# Control.net
KiCad netlist of a schematic drawn in EAGLE
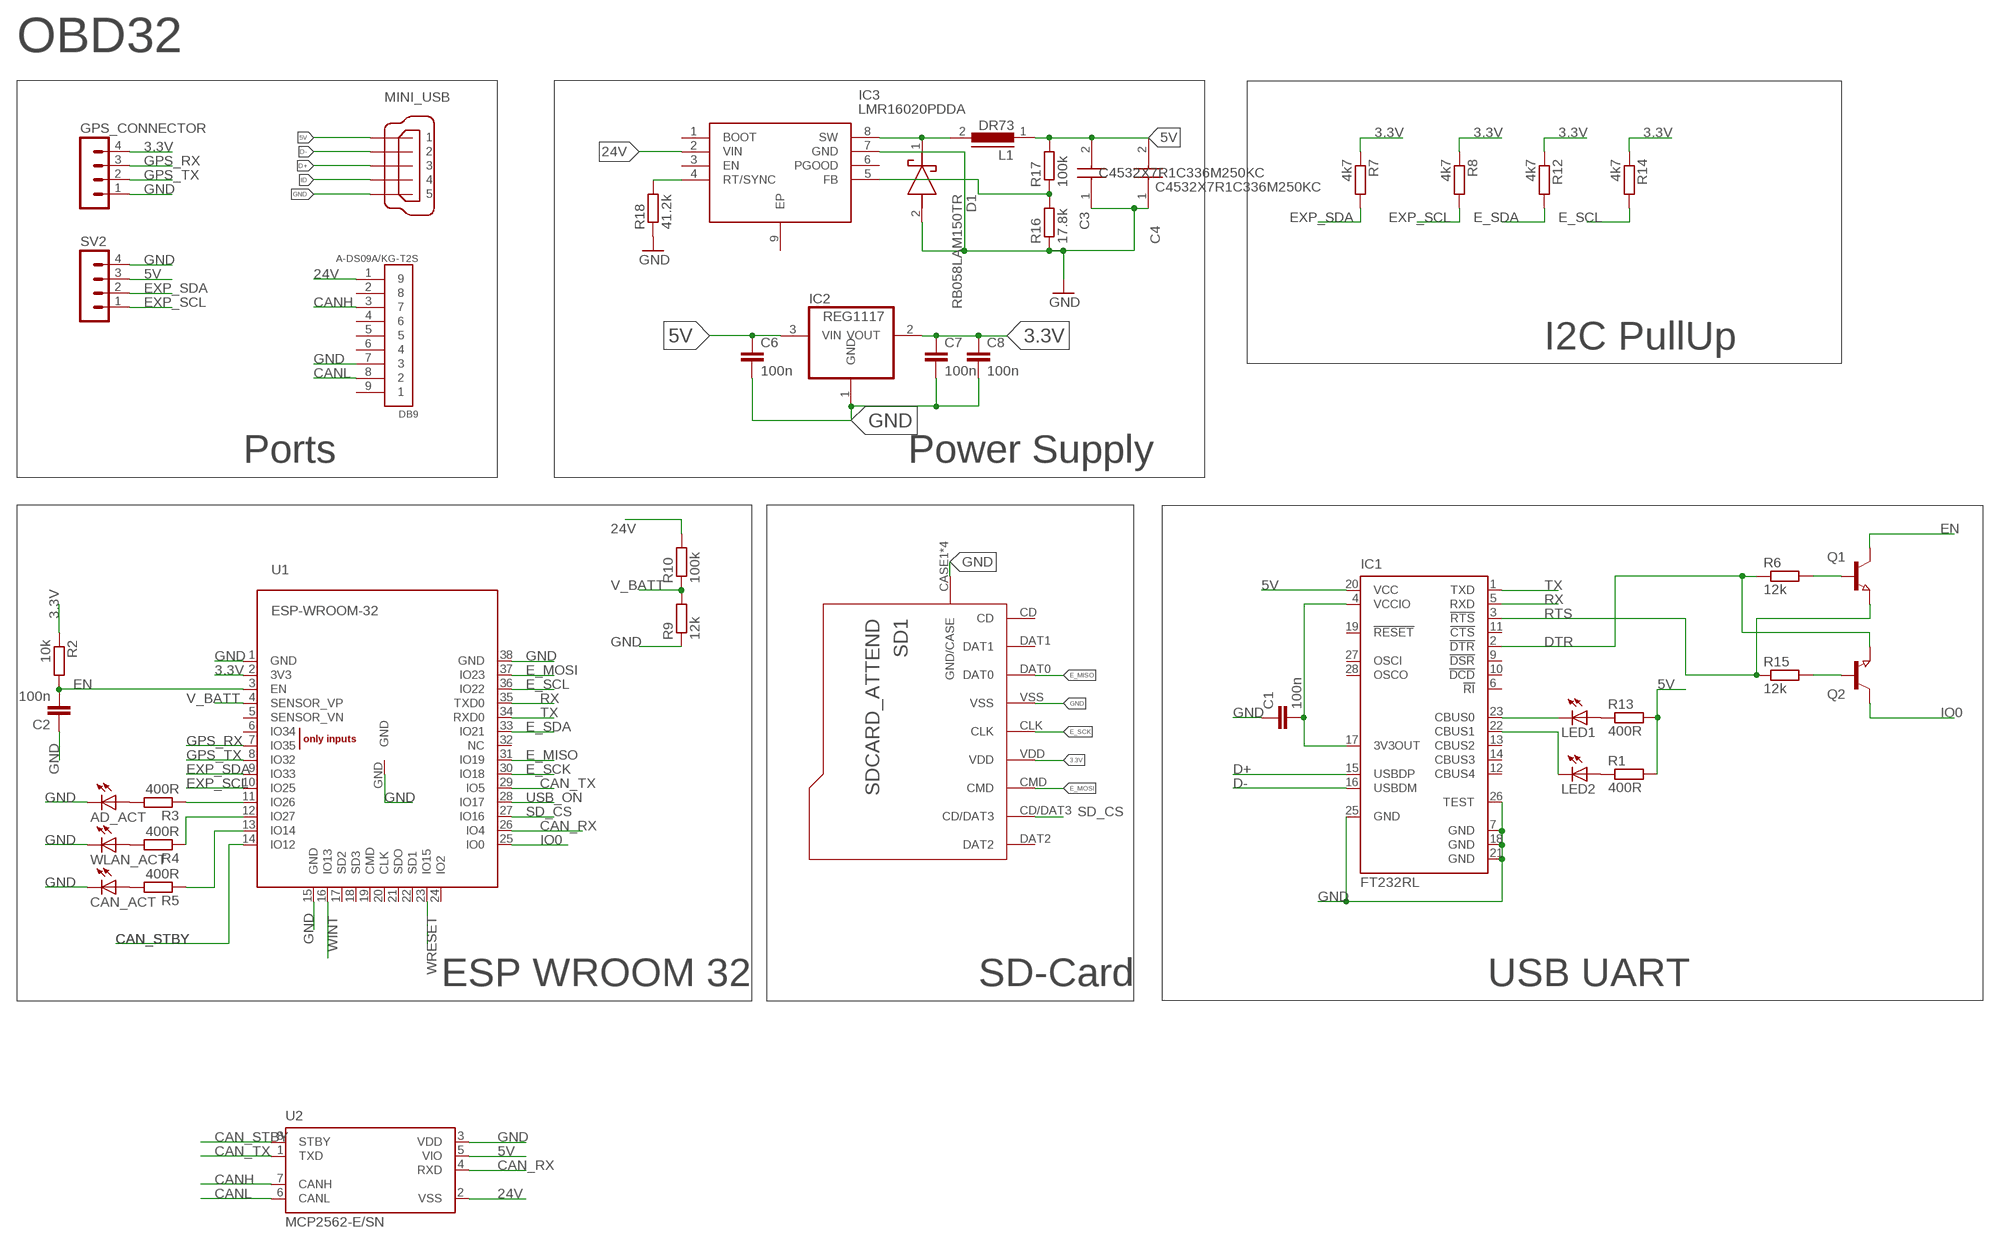
[diagram p0: schematic, sheet 1]

(export (version "E")
  (design (tool "Eeschema 10.0.6"))
  (components
    (comp (ref "AD_ACT")
      (value "LEDCHIP-LED0805")
      (footprint "eagle-import:CHIP-LED0805")
      (libsource (lib "eagle-import") (part "LEDCHIP-LED0805"))
    )
    (comp (ref "C1")
      (value "100n")
      (footprint "eagle-import:C0805")
      (libsource (lib "eagle-import") (part "C-EUC0805"))
    )
    (comp (ref "C2")
      (value "100n")
      (footprint "eagle-import:C0805")
      (libsource (lib "eagle-import") (part "C-EUC0805"))
    )
    (comp (ref "C3")
      (value "C4532X7R1C336M250KC")
      (footprint "eagle-import:CAPC4532X360N")
      (fields (field (name "MOUSER_PART_NUMBER") "810-C4532X7R1C336M"))
      (libsource (lib "eagle-import") (part "C4532X7R1C336M250KC"))
    )
    (comp (ref "C4")
      (value "C4532X7R1C336M250KC")
      (footprint "eagle-import:CAPC4532X360N")
      (fields (field (name "MOUSER_PART_NUMBER") "810-C4532X7R1C336M"))
      (libsource (lib "eagle-import") (part "C4532X7R1C336M250KC"))
    )
    (comp (ref "C6")
      (value "100n")
      (footprint "eagle-import:C0805")
      (libsource (lib "eagle-import") (part "C-EUC0805"))
    )
    (comp (ref "C7")
      (value "100n")
      (footprint "eagle-import:C0805")
      (libsource (lib "eagle-import") (part "C-EUC0805"))
    )
    (comp (ref "C8")
      (value "100n")
      (footprint "eagle-import:C0805")
      (libsource (lib "eagle-import") (part "C-EUC0805"))
    )
    (comp (ref "CAN_ACT")
      (value "LEDCHIP-LED0805")
      (footprint "eagle-import:CHIP-LED0805")
      (libsource (lib "eagle-import") (part "LEDCHIP-LED0805"))
    )
    (comp (ref "D1")
      (value "RB058LAM150TR")
      (footprint "eagle-import:SODFL4725X105N")
      (fields (field (name "MOUSER_PART_NUMBER") "755-RB058LAM150TR"))
      (libsource (lib "eagle-import") (part "RB058LAM150TR"))
    )
    (comp (ref "DB9")
      (value "A-DS09A/KG-T2S")
      (footprint "eagle-import:A-DS09A_KG-T2S")
      (fields
        (field (name "DIGI_KEY_PART_NUMBER") "AE10968-ND")
        (field (name "MANUFACTURER") "Assmann WSW Components")
        (field (name "MPN") "A-DS 09 A/KG-T2S")
        (field (name "CREATEDBY") "PCBLayout.com")
      )
      (libsource (lib "eagle-import") (part "A-DS09A/KG-T2S"))
    )
    (comp (ref "GPS_CONNECTOR")
      (value "MA04-1")
      (footprint "eagle-import:MA04-1")
      (libsource (lib "eagle-import") (part "MA04-1"))
    )
    (comp (ref "IC1")
      (value "FT232RL")
      (footprint "eagle-import:SSOP28")
      (libsource (lib "eagle-import") (part "FT232RL"))
    )
    (comp (ref "IC2")
      (value "REG1117")
      (footprint "eagle-import:SOT223")
      (libsource (lib "eagle-import") (part "REG1117"))
    )
    (comp (ref "IC3")
      (value "LMR16020PDDA")
      (footprint "eagle-import:SOIC127P600X170-9N")
      (fields (field (name "MOUSER_PART_NUMBER") "595-LMR16020PDDA"))
      (libsource (lib "eagle-import") (part "LMR16020PDDA"))
    )
    (comp (ref "L1")
      (value "DR73")
      (footprint "eagle-import:DR73")
      (libsource (lib "eagle-import") (part "DR73"))
    )
    (comp (ref "LED1")
      (value "LEDCHIPLED_0805")
      (footprint "eagle-import:CHIPLED_0805")
      (libsource (lib "eagle-import") (part "LEDCHIPLED_0805"))
    )
    (comp (ref "LED2")
      (value "LEDCHIPLED_0805")
      (footprint "eagle-import:CHIPLED_0805")
      (libsource (lib "eagle-import") (part "LEDCHIPLED_0805"))
    )
    (comp (ref "MINI_USB")
      (value "MINI-USB-32005-301")
      (footprint "eagle-import:32005-301")
      (libsource (lib "eagle-import") (part "MINI-USB-32005-301"))
    )
    (comp (ref "Q1")
      (value "NPN-TRANSISTOR_SOT23")
      (footprint "eagle-import:SOT23")
      (libsource (lib "eagle-import") (part "NPN-TRANSISTOR_SOT23"))
    )
    (comp (ref "Q2")
      (value "NPN-TRANSISTOR_SOT23")
      (footprint "eagle-import:SOT23")
      (libsource (lib "eagle-import") (part "NPN-TRANSISTOR_SOT23"))
    )
    (comp (ref "R1")
      (value "400R")
      (footprint "eagle-import:R0805")
      (libsource (lib "eagle-import") (part "R-EU_R0805"))
    )
    (comp (ref "R2")
      (value "10k")
      (footprint "eagle-import:R0805")
      (libsource (lib "eagle-import") (part "R-EU_R0805"))
    )
    (comp (ref "R3")
      (value "400R")
      (footprint "eagle-import:R0805")
      (libsource (lib "eagle-import") (part "R-EU_R0805"))
    )
    (comp (ref "R4")
      (value "400R")
      (footprint "eagle-import:R0805")
      (libsource (lib "eagle-import") (part "R-EU_R0805"))
    )
    (comp (ref "R5")
      (value "400R")
      (footprint "eagle-import:R0805")
      (libsource (lib "eagle-import") (part "R-EU_R0805"))
    )
    (comp (ref "R6")
      (value "12k")
      (footprint "eagle-import:R0805")
      (libsource (lib "eagle-import") (part "R-EU_R0805"))
    )
    (comp (ref "R7")
      (value "4k7")
      (footprint "eagle-import:R0805")
      (libsource (lib "eagle-import") (part "R-EU_R0805"))
    )
    (comp (ref "R8")
      (value "4k7")
      (footprint "eagle-import:R0805")
      (libsource (lib "eagle-import") (part "R-EU_R0805"))
    )
    (comp (ref "R9")
      (value "12k")
      (footprint "eagle-import:R0805")
      (libsource (lib "eagle-import") (part "R-EU_R0805"))
    )
    (comp (ref "R10")
      (value "100k")
      (footprint "eagle-import:R0805")
      (libsource (lib "eagle-import") (part "R-EU_R0805"))
    )
    (comp (ref "R12")
      (value "4k7")
      (footprint "eagle-import:R0805")
      (libsource (lib "eagle-import") (part "R-EU_R0805"))
    )
    (comp (ref "R13")
      (value "400R")
      (footprint "eagle-import:R0805")
      (libsource (lib "eagle-import") (part "R-EU_R0805"))
    )
    (comp (ref "R14")
      (value "4k7")
      (footprint "eagle-import:R0805")
      (libsource (lib "eagle-import") (part "R-EU_R0805"))
    )
    (comp (ref "R15")
      (value "12k")
      (footprint "eagle-import:R0805")
      (libsource (lib "eagle-import") (part "R-EU_R0805"))
    )
    (comp (ref "R16")
      (value "17.8k")
      (footprint "eagle-import:R0805")
      (libsource (lib "eagle-import") (part "R-EU_R0805"))
    )
    (comp (ref "R17")
      (value "100k")
      (footprint "eagle-import:R0805")
      (libsource (lib "eagle-import") (part "R-EU_R0805"))
    )
    (comp (ref "R18")
      (value "41.2k")
      (footprint "eagle-import:R0805")
      (libsource (lib "eagle-import") (part "R-EU_R0805"))
    )
    (comp (ref "SD1")
      (value "SDCARD_ATTEND")
      (footprint "eagle-import:SD_ATTEND")
      (libsource (lib "eagle-import") (part "SDCARD_ATTEND"))
    )
    (comp (ref "SV2")
      (value "MA04-1")
      (footprint "eagle-import:MA04-1")
      (libsource (lib "eagle-import") (part "MA04-1"))
    )
    (comp (ref "U1")
      (value "ESP-WROOM-32")
      (footprint "eagle-import:ESP-WROOM-32")
      (libsource (lib "eagle-import") (part "ESP-WROOM-32"))
    )
    (comp (ref "U2")
      (value "MCP2562-E/SN")
      (footprint "eagle-import:SOIC127P600X175-8N")
      (fields (field (name "MF") "Microchip"))
      (libsource (lib "eagle-import") (part "MCP2562-E/SN"))
    )
    (comp (ref "WLAN_ACT")
      (value "LEDCHIP-LED0805")
      (footprint "eagle-import:CHIP-LED0805")
      (libsource (lib "eagle-import") (part "LEDCHIP-LED0805"))
    )
  )
  (nets
    (net (code "1") (name "/CANH") (class "Default")
      (node (ref "DB9") (pin "3") (pinfunction "7_3") (pintype "passive"))
      (node (ref "U2") (pin "7") (pinfunction "CANH_7") (pintype "input"))
    )
    (net (code "2") (name "/CANL") (class "Default")
      (node (ref "DB9") (pin "8") (pinfunction "2_8") (pintype "passive"))
      (node (ref "U2") (pin "6") (pinfunction "CANL_6") (pintype "input"))
    )
    (net (code "3") (name "/CAN_RX") (class "Default")
      (node (ref "U1") (pin "26") (pinfunction "IO4_26") (pintype "bidirectional"))
      (node (ref "U2") (pin "4") (pinfunction "RXD_4") (pintype "output"))
    )
    (net (code "4") (name "/CAN_STBY") (class "Default")
      (node (ref "U1") (pin "14") (pinfunction "IO12_14") (pintype "bidirectional"))
      (node (ref "U2") (pin "8") (pinfunction "STBY_8") (pintype "input"))
    )
    (net (code "5") (name "/CAN_TX") (class "Default")
      (node (ref "U1") (pin "29") (pinfunction "IO5_29") (pintype "bidirectional"))
      (node (ref "U2") (pin "1") (pinfunction "TXD_1") (pintype "input"))
    )
    (net (code "6") (name "/DTR") (class "Default")
      (node (ref "IC1") (pin "2") (pinfunction "~{DTR}_2") (pintype "output"))
      (node (ref "Q2") (pin "2") (pinfunction "E_2") (pintype "passive"))
      (node (ref "R6") (pin "1") (pinfunction "1_1") (pintype "passive"))
    )
    (net (code "7") (name "/EN") (class "Default")
      (node (ref "C2") (pin "2") (pinfunction "2_2") (pintype "passive"))
      (node (ref "Q1") (pin "3") (pinfunction "C_3") (pintype "passive"))
      (node (ref "R2") (pin "2") (pinfunction "2_2") (pintype "passive"))
      (node (ref "U1") (pin "3") (pinfunction "EN_3") (pintype "bidirectional"))
    )
    (net (code "8") (name "/EXP_SCL") (class "Default")
      (node (ref "R8") (pin "2") (pinfunction "2_2") (pintype "passive"))
      (node (ref "SV2") (pin "1") (pinfunction "1_1") (pintype "passive"))
      (node (ref "U1") (pin "10") (pinfunction "IO25_10") (pintype "bidirectional"))
    )
    (net (code "9") (name "/EXP_SDA") (class "Default")
      (node (ref "R7") (pin "2") (pinfunction "2_2") (pintype "passive"))
      (node (ref "SV2") (pin "2") (pinfunction "2_2") (pintype "passive"))
      (node (ref "U1") (pin "9") (pinfunction "IO33_9") (pintype "bidirectional"))
    )
    (net (code "10") (name "/E_SCL") (class "Default")
      (node (ref "R14") (pin "2") (pinfunction "2_2") (pintype "passive"))
      (node (ref "U1") (pin "36") (pinfunction "IO22_36") (pintype "bidirectional"))
    )
    (net (code "11") (name "/E_SDA") (class "Default")
      (node (ref "R12") (pin "2") (pinfunction "2_2") (pintype "passive"))
      (node (ref "U1") (pin "33") (pinfunction "IO21_33") (pintype "bidirectional"))
    )
    (net (code "12") (name "/GPS_RX") (class "Default")
      (node (ref "GPS_CONNECTOR") (pin "3") (pinfunction "3_3") (pintype "passive"))
      (node (ref "U1") (pin "7") (pinfunction "IO35_7") (pintype "input"))
    )
    (net (code "13") (name "/GPS_TX") (class "Default")
      (node (ref "GPS_CONNECTOR") (pin "2") (pinfunction "2_2") (pintype "passive"))
      (node (ref "U1") (pin "8") (pinfunction "IO32_8") (pintype "bidirectional"))
    )
    (net (code "14") (name "/IO0") (class "Default")
      (node (ref "Q2") (pin "3") (pinfunction "C_3") (pintype "passive"))
      (node (ref "U1") (pin "25") (pinfunction "IO0_25") (pintype "bidirectional"))
    )
    (net (code "15") (name "/RTS") (class "Default")
      (node (ref "IC1") (pin "3") (pinfunction "~{RTS}_3") (pintype "output"))
      (node (ref "Q1") (pin "2") (pinfunction "E_2") (pintype "passive"))
      (node (ref "R15") (pin "1") (pinfunction "1_1") (pintype "passive"))
    )
    (net (code "16") (name "/RX") (class "Default")
      (node (ref "IC1") (pin "5") (pinfunction "RXD_5") (pintype "input"))
      (node (ref "U1") (pin "35") (pinfunction "TXD0_35") (pintype "bidirectional"))
    )
    (net (code "17") (name "/SD_CS") (class "Default")
      (node (ref "SD1") (pin "CD/DAT3") (pinfunction "CD/DAT3_CD/DAT3") (pintype "bidirectional"))
      (node (ref "U1") (pin "27") (pinfunction "IO16_27") (pintype "bidirectional"))
    )
    (net (code "18") (name "/TX") (class "Default")
      (node (ref "IC1") (pin "1") (pinfunction "TXD_1") (pintype "output"))
      (node (ref "U1") (pin "34") (pinfunction "RXD0_34") (pintype "bidirectional"))
    )
    (net (code "19") (name "/USB_ON") (class "Default")
      (node (ref "U1") (pin "28") (pinfunction "IO17_28") (pintype "bidirectional"))
    )
    (net (code "20") (name "/V_BATT") (class "Default")
      (node (ref "R10") (pin "1") (pinfunction "1_1") (pintype "passive"))
      (node (ref "R9") (pin "2") (pinfunction "2_2") (pintype "passive"))
      (node (ref "U1") (pin "4") (pinfunction "SENSOR_VP_4") (pintype "input"))
    )
    (net (code "21") (name "/WINT") (class "Default")
      (node (ref "U1") (pin "16") (pinfunction "IO13_16") (pintype "bidirectional"))
    )
    (net (code "22") (name "/WRESET") (class "Default")
      (node (ref "U1") (pin "23") (pinfunction "IO15_23") (pintype "bidirectional"))
    )
    (net (code "23") (name "3.3V") (class "Default")
      (node (ref "C7") (pin "1") (pinfunction "1_1") (pintype "passive"))
      (node (ref "C8") (pin "1") (pinfunction "1_1") (pintype "passive"))
      (node (ref "GPS_CONNECTOR") (pin "4") (pinfunction "4_4") (pintype "passive"))
      (node (ref "IC2") (pin "2") (pinfunction "VOUT_2") (pintype "output"))
      (node (ref "R12") (pin "1") (pinfunction "1_1") (pintype "passive"))
      (node (ref "R14") (pin "1") (pinfunction "1_1") (pintype "passive"))
      (node (ref "R2") (pin "1") (pinfunction "1_1") (pintype "passive"))
      (node (ref "R7") (pin "1") (pinfunction "1_1") (pintype "passive"))
      (node (ref "R8") (pin "1") (pinfunction "1_1") (pintype "passive"))
      (node (ref "SD1") (pin "VDD") (pinfunction "VDD_VDD") (pintype "bidirectional"))
      (node (ref "U1") (pin "2") (pinfunction "3V3_2") (pintype "bidirectional"))
    )
    (net (code "24") (name "5V") (class "Default")
      (node (ref "C3") (pin "2") (pinfunction "2_2") (pintype "bidirectional"))
      (node (ref "C4") (pin "2") (pinfunction "2_2") (pintype "bidirectional"))
      (node (ref "C6") (pin "1") (pinfunction "1_1") (pintype "passive"))
      (node (ref "IC1") (pin "20") (pinfunction "VCC_20") (pintype "power_in"))
      (node (ref "IC2") (pin "3") (pinfunction "VIN_3") (pintype "input"))
      (node (ref "L1") (pin "1") (pinfunction "1_1") (pintype "passive"))
      (node (ref "MINI_USB") (pin "1") (pinfunction "1_1") (pintype "passive"))
      (node (ref "R1") (pin "2") (pinfunction "2_2") (pintype "passive"))
      (node (ref "R13") (pin "2") (pinfunction "2_2") (pintype "passive"))
      (node (ref "R17") (pin "2") (pinfunction "2_2") (pintype "passive"))
      (node (ref "SV2") (pin "3") (pinfunction "3_3") (pintype "passive"))
      (node (ref "U2") (pin "5") (pinfunction "VIO_5") (pintype "power_in"))
    )
    (net (code "25") (name "24V") (class "Default")
      (node (ref "DB9") (pin "1") (pinfunction "9_1") (pintype "passive"))
      (node (ref "IC3") (pin "2") (pinfunction "VIN_2") (pintype "bidirectional"))
      (node (ref "R10") (pin "2") (pinfunction "2_2") (pintype "passive"))
      (node (ref "U2") (pin "2") (pinfunction "VSS_2") (pintype "power_in"))
    )
    (net (code "26") (name "D+") (class "Default")
      (node (ref "IC1") (pin "15") (pinfunction "USBDP_15") (pintype "bidirectional"))
      (node (ref "MINI_USB") (pin "3") (pinfunction "3_3") (pintype "passive"))
    )
    (net (code "27") (name "D-") (class "Default")
      (node (ref "IC1") (pin "16") (pinfunction "USBDM_16") (pintype "bidirectional"))
      (node (ref "MINI_USB") (pin "2") (pinfunction "2_2") (pintype "passive"))
    )
    (net (code "28") (name "E_MISO") (class "Default")
      (node (ref "SD1") (pin "DAT0") (pinfunction "DAT0_DAT0") (pintype "bidirectional"))
      (node (ref "U1") (pin "31") (pinfunction "IO19_31") (pintype "bidirectional"))
    )
    (net (code "29") (name "E_MOSI") (class "Default")
      (node (ref "SD1") (pin "CMD") (pinfunction "CMD_CMD") (pintype "bidirectional"))
      (node (ref "U1") (pin "37") (pinfunction "IO23_37") (pintype "bidirectional"))
    )
    (net (code "30") (name "E_SCK") (class "Default")
      (node (ref "SD1") (pin "CLK") (pinfunction "CLK_CLK") (pintype "bidirectional"))
      (node (ref "U1") (pin "30") (pinfunction "IO18_30") (pintype "bidirectional"))
    )
    (net (code "31") (name "GND") (class "Default")
      (node (ref "AD_ACT") (pin "C") (pinfunction "C_C") (pintype "passive"))
      (node (ref "C1") (pin "1") (pinfunction "1_1") (pintype "passive"))
      (node (ref "C2") (pin "1") (pinfunction "1_1") (pintype "passive"))
      (node (ref "C3") (pin "1") (pinfunction "1_1") (pintype "bidirectional"))
      (node (ref "C4") (pin "1") (pinfunction "1_1") (pintype "bidirectional"))
      (node (ref "C6") (pin "2") (pinfunction "2_2") (pintype "passive"))
      (node (ref "C7") (pin "2") (pinfunction "2_2") (pintype "passive"))
      (node (ref "C8") (pin "2") (pinfunction "2_2") (pintype "passive"))
      (node (ref "CAN_ACT") (pin "C") (pinfunction "C_C") (pintype "passive"))
      (node (ref "D1") (pin "2") (pinfunction "A_2") (pintype "bidirectional"))
      (node (ref "DB9") (pin "7") (pinfunction "3_7") (pintype "passive"))
      (node (ref "GPS_CONNECTOR") (pin "1") (pinfunction "1_1") (pintype "passive"))
      (node (ref "IC1") (pin "18") (pinfunction "GND_18") (pintype "power_in"))
      (node (ref "IC1") (pin "21") (pinfunction "GND_21") (pintype "power_in"))
      (node (ref "IC1") (pin "25") (pinfunction "GND_25") (pintype "power_in"))
      (node (ref "IC1") (pin "26") (pinfunction "TEST_26") (pintype "input"))
      (node (ref "IC1") (pin "7") (pinfunction "GND_7") (pintype "power_in"))
      (node (ref "IC2") (pin "1") (pinfunction "GND_1") (pintype "power_in"))
      (node (ref "IC3") (pin "7") (pinfunction "GND_7") (pintype "bidirectional"))
      (node (ref "MINI_USB") (pin "5") (pinfunction "5_5") (pintype "passive"))
      (node (ref "R16") (pin "1") (pinfunction "1_1") (pintype "passive"))
      (node (ref "R18") (pin "1") (pinfunction "1_1") (pintype "passive"))
      (node (ref "R9") (pin "1") (pinfunction "1_1") (pintype "passive"))
      (node (ref "SD1") (pin "CASE1") (pinfunction "GND/CASE_CASE1") (pintype "bidirectional"))
      (node (ref "SD1") (pin "CASE2") (pinfunction "GND/CASE_CASE2") (pintype "bidirectional"))
      (node (ref "SD1") (pin "CASE3") (pinfunction "GND/CASE_CASE3") (pintype "bidirectional"))
      (node (ref "SD1") (pin "CASE4") (pinfunction "GND/CASE_CASE4") (pintype "bidirectional"))
      (node (ref "SD1") (pin "VSS") (pinfunction "VSS_VSS") (pintype "bidirectional"))
      (node (ref "SV2") (pin "4") (pinfunction "4_4") (pintype "passive"))
      (node (ref "U1") (pin "1") (pinfunction "GND_1") (pintype "bidirectional"))
      (node (ref "U1") (pin "15") (pinfunction "GND_15") (pintype "bidirectional"))
      (node (ref "U1") (pin "38") (pinfunction "GND_38") (pintype "bidirectional"))
      (node (ref "U1") (pin "GND") (pinfunction "GND_GND") (pintype "bidirectional"))
      (node (ref "U2") (pin "3") (pinfunction "VDD_3") (pintype "power_in"))
      (node (ref "WLAN_ACT") (pin "C") (pinfunction "C_C") (pintype "passive"))
    )
    (net (code "32") (name "ID") (class "Default")
      (node (ref "MINI_USB") (pin "4") (pinfunction "4_4") (pintype "passive"))
    )
    (net (code "33") (name "Net-(AD_ACT-PadA)") (class "Default")
      (node (ref "AD_ACT") (pin "A") (pinfunction "A_A") (pintype "passive"))
      (node (ref "R3") (pin "2") (pinfunction "2_2") (pintype "passive"))
    )
    (net (code "34") (name "Net-(CAN_ACT-PadA)") (class "Default")
      (node (ref "CAN_ACT") (pin "A") (pinfunction "A_A") (pintype "passive"))
      (node (ref "R5") (pin "2") (pinfunction "2_2") (pintype "passive"))
    )
    (net (code "35") (name "Net-(D1-K)") (class "Default")
      (node (ref "D1") (pin "1") (pinfunction "K_1") (pintype "bidirectional"))
      (node (ref "IC3") (pin "8") (pinfunction "SW_8") (pintype "bidirectional"))
      (node (ref "L1") (pin "2") (pinfunction "2_2") (pintype "passive"))
    )
    (net (code "36") (name "Net-(IC1-3V3OUT)") (class "Default")
      (node (ref "C1") (pin "2") (pinfunction "2_2") (pintype "passive"))
      (node (ref "IC1") (pin "17") (pinfunction "3V3OUT_17") (pintype "output"))
      (node (ref "IC1") (pin "4") (pinfunction "VCCIO_4") (pintype "power_in"))
    )
    (net (code "37") (name "Net-(IC1-CBUS0)") (class "Default")
      (node (ref "IC1") (pin "23") (pinfunction "CBUS0_23") (pintype "bidirectional"))
      (node (ref "LED1") (pin "C") (pinfunction "C_C") (pintype "passive"))
    )
    (net (code "38") (name "Net-(IC1-CBUS1)") (class "Default")
      (node (ref "IC1") (pin "22") (pinfunction "CBUS1_22") (pintype "bidirectional"))
      (node (ref "LED2") (pin "C") (pinfunction "C_C") (pintype "passive"))
    )
    (net (code "39") (name "Net-(IC3-FB)") (class "Default")
      (node (ref "IC3") (pin "5") (pinfunction "FB_5") (pintype "bidirectional"))
      (node (ref "R16") (pin "2") (pinfunction "2_2") (pintype "passive"))
      (node (ref "R17") (pin "1") (pinfunction "1_1") (pintype "passive"))
    )
    (net (code "40") (name "Net-(IC3-RT{slash}SYNC)") (class "Default")
      (node (ref "IC3") (pin "4") (pinfunction "RT/SYNC_4") (pintype "bidirectional"))
      (node (ref "R18") (pin "2") (pinfunction "2_2") (pintype "passive"))
    )
    (net (code "41") (name "Net-(LED1-PadA)") (class "Default")
      (node (ref "LED1") (pin "A") (pinfunction "A_A") (pintype "passive"))
      (node (ref "R13") (pin "1") (pinfunction "1_1") (pintype "passive"))
    )
    (net (code "42") (name "Net-(LED2-PadA)") (class "Default")
      (node (ref "LED2") (pin "A") (pinfunction "A_A") (pintype "passive"))
      (node (ref "R1") (pin "1") (pinfunction "1_1") (pintype "passive"))
    )
    (net (code "43") (name "Net-(Q1-B)") (class "Default")
      (node (ref "Q1") (pin "1") (pinfunction "B_1") (pintype "passive"))
      (node (ref "R6") (pin "2") (pinfunction "2_2") (pintype "passive"))
    )
    (net (code "44") (name "Net-(Q2-B)") (class "Default")
      (node (ref "Q2") (pin "1") (pinfunction "B_1") (pintype "passive"))
      (node (ref "R15") (pin "2") (pinfunction "2_2") (pintype "passive"))
    )
    (net (code "45") (name "Net-(R4-Pad2)") (class "Default")
      (node (ref "R4") (pin "2") (pinfunction "2_2") (pintype "passive"))
      (node (ref "WLAN_ACT") (pin "A") (pinfunction "A_A") (pintype "passive"))
    )
    (net (code "46") (name "Net-(U1-IO14)") (class "Default")
      (node (ref "R5") (pin "1") (pinfunction "1_1") (pintype "passive"))
      (node (ref "U1") (pin "13") (pinfunction "IO14_13") (pintype "bidirectional"))
    )
    (net (code "47") (name "Net-(U1-IO26)") (class "Default")
      (node (ref "R3") (pin "1") (pinfunction "1_1") (pintype "passive"))
      (node (ref "U1") (pin "11") (pinfunction "IO26_11") (pintype "bidirectional"))
    )
    (net (code "48") (name "Net-(U1-IO27)") (class "Default")
      (node (ref "R4") (pin "1") (pinfunction "1_1") (pintype "passive"))
      (node (ref "U1") (pin "12") (pinfunction "IO27_12") (pintype "bidirectional"))
    )
    (net (code "49") (name "unconnected-(DB9-1-Pad9)") (class "Default")
      (node (ref "DB9") (pin "9") (pinfunction "1_9") (pintype "passive"))
    )
    (net (code "50") (name "unconnected-(DB9-4-Pad6)") (class "Default")
      (node (ref "DB9") (pin "6") (pinfunction "4_6") (pintype "passive"))
    )
    (net (code "51") (name "unconnected-(DB9-6-Pad4)") (class "Default")
      (node (ref "DB9") (pin "4") (pinfunction "6_4") (pintype "passive"))
    )
    (net (code "52") (name "unconnected-(DB9-8-Pad2)") (class "Default")
      (node (ref "DB9") (pin "2") (pinfunction "8_2") (pintype "passive"))
    )
    (net (code "53") (name "unconnected-(DB9-Pad5)") (class "Default")
      (node (ref "DB9") (pin "5") (pinfunction "5_5") (pintype "passive"))
    )
    (net (code "54") (name "unconnected-(IC1-CBUS2-Pad13)") (class "Default")
      (node (ref "IC1") (pin "13") (pinfunction "CBUS2_13") (pintype "bidirectional"))
    )
    (net (code "55") (name "unconnected-(IC1-CBUS3-Pad14)") (class "Default")
      (node (ref "IC1") (pin "14") (pinfunction "CBUS3_14") (pintype "bidirectional"))
    )
    (net (code "56") (name "unconnected-(IC1-CBUS4-Pad12)") (class "Default")
      (node (ref "IC1") (pin "12") (pinfunction "CBUS4_12") (pintype "bidirectional"))
    )
    (net (code "57") (name "unconnected-(IC1-OSCI-Pad27)") (class "Default")
      (node (ref "IC1") (pin "27") (pinfunction "OSCI_27") (pintype "input"))
    )
    (net (code "58") (name "unconnected-(IC1-OSCO-Pad28)") (class "Default")
      (node (ref "IC1") (pin "28") (pinfunction "OSCO_28") (pintype "output"))
    )
    (net (code "59") (name "unconnected-(IC1-~{CTS}-Pad11)") (class "Default")
      (node (ref "IC1") (pin "11") (pinfunction "~{CTS}_11") (pintype "input"))
    )
    (net (code "60") (name "unconnected-(IC1-~{DCD}-Pad10)") (class "Default")
      (node (ref "IC1") (pin "10") (pinfunction "~{DCD}_10") (pintype "input"))
    )
    (net (code "61") (name "unconnected-(IC1-~{DSR}-Pad9)") (class "Default")
      (node (ref "IC1") (pin "9") (pinfunction "~{DSR}_9") (pintype "input"))
    )
    (net (code "62") (name "unconnected-(IC1-~{RESET}-Pad19)") (class "Default")
      (node (ref "IC1") (pin "19") (pinfunction "~{RESET}_19") (pintype "input"))
    )
    (net (code "63") (name "unconnected-(IC1-~{RI}-Pad6)") (class "Default")
      (node (ref "IC1") (pin "6") (pinfunction "~{RI}_6") (pintype "input"))
    )
    (net (code "64") (name "unconnected-(IC3-BOOT-Pad1)") (class "Default")
      (node (ref "IC3") (pin "1") (pinfunction "BOOT_1") (pintype "bidirectional"))
    )
    (net (code "65") (name "unconnected-(IC3-EN-Pad3)") (class "Default")
      (node (ref "IC3") (pin "3") (pinfunction "EN_3") (pintype "bidirectional"))
    )
    (net (code "66") (name "unconnected-(IC3-EP-Pad9)") (class "Default")
      (node (ref "IC3") (pin "9") (pinfunction "EP_9") (pintype "bidirectional"))
    )
    (net (code "67") (name "unconnected-(IC3-PGOOD-Pad6)") (class "Default")
      (node (ref "IC3") (pin "6") (pinfunction "PGOOD_6") (pintype "bidirectional"))
    )
    (net (code "68") (name "unconnected-(SD1-PadCD)") (class "Default")
      (node (ref "SD1") (pin "CD") (pinfunction "CD_CD") (pintype "bidirectional"))
    )
    (net (code "69") (name "unconnected-(SD1-PadDAT1)") (class "Default")
      (node (ref "SD1") (pin "DAT1") (pinfunction "DAT1_DAT1") (pintype "bidirectional"))
    )
    (net (code "70") (name "unconnected-(SD1-PadDAT2)") (class "Default")
      (node (ref "SD1") (pin "DAT2") (pinfunction "DAT2_DAT2") (pintype "bidirectional"))
    )
    (net (code "71") (name "unconnected-(U1-CLK-Pad20)") (class "Default")
      (node (ref "U1") (pin "20") (pinfunction "CLK_20") (pintype "bidirectional"))
    )
    (net (code "72") (name "unconnected-(U1-CMD-Pad19)") (class "Default")
      (node (ref "U1") (pin "19") (pinfunction "CMD_19") (pintype "bidirectional"))
    )
    (net (code "73") (name "unconnected-(U1-IO2-Pad24)") (class "Default")
      (node (ref "U1") (pin "24") (pinfunction "IO2_24") (pintype "bidirectional"))
    )
    (net (code "74") (name "unconnected-(U1-IO34-Pad6)") (class "Default")
      (node (ref "U1") (pin "6") (pinfunction "IO34_6") (pintype "input"))
    )
    (net (code "75") (name "unconnected-(U1-NC-Pad32)") (class "Default")
      (node (ref "U1") (pin "32") (pinfunction "NC_32") (pintype "bidirectional"))
    )
    (net (code "76") (name "unconnected-(U1-SD1-Pad22)") (class "Default")
      (node (ref "U1") (pin "22") (pinfunction "SD1_22") (pintype "bidirectional"))
    )
    (net (code "77") (name "unconnected-(U1-SD2-Pad17)") (class "Default")
      (node (ref "U1") (pin "17") (pinfunction "SD2_17") (pintype "bidirectional"))
    )
    (net (code "78") (name "unconnected-(U1-SD3-Pad18)") (class "Default")
      (node (ref "U1") (pin "18") (pinfunction "SD3_18") (pintype "bidirectional"))
    )
    (net (code "79") (name "unconnected-(U1-SDO-Pad21)") (class "Default")
      (node (ref "U1") (pin "21") (pinfunction "SDO_21") (pintype "bidirectional"))
    )
    (net (code "80") (name "unconnected-(U1-SENSOR_VN-Pad5)") (class "Default")
      (node (ref "U1") (pin "5") (pinfunction "SENSOR_VN_5") (pintype "input"))
    )
  )
)
